# PCBschematic.net
KiCad netlist of a schematic drawn in EAGLE
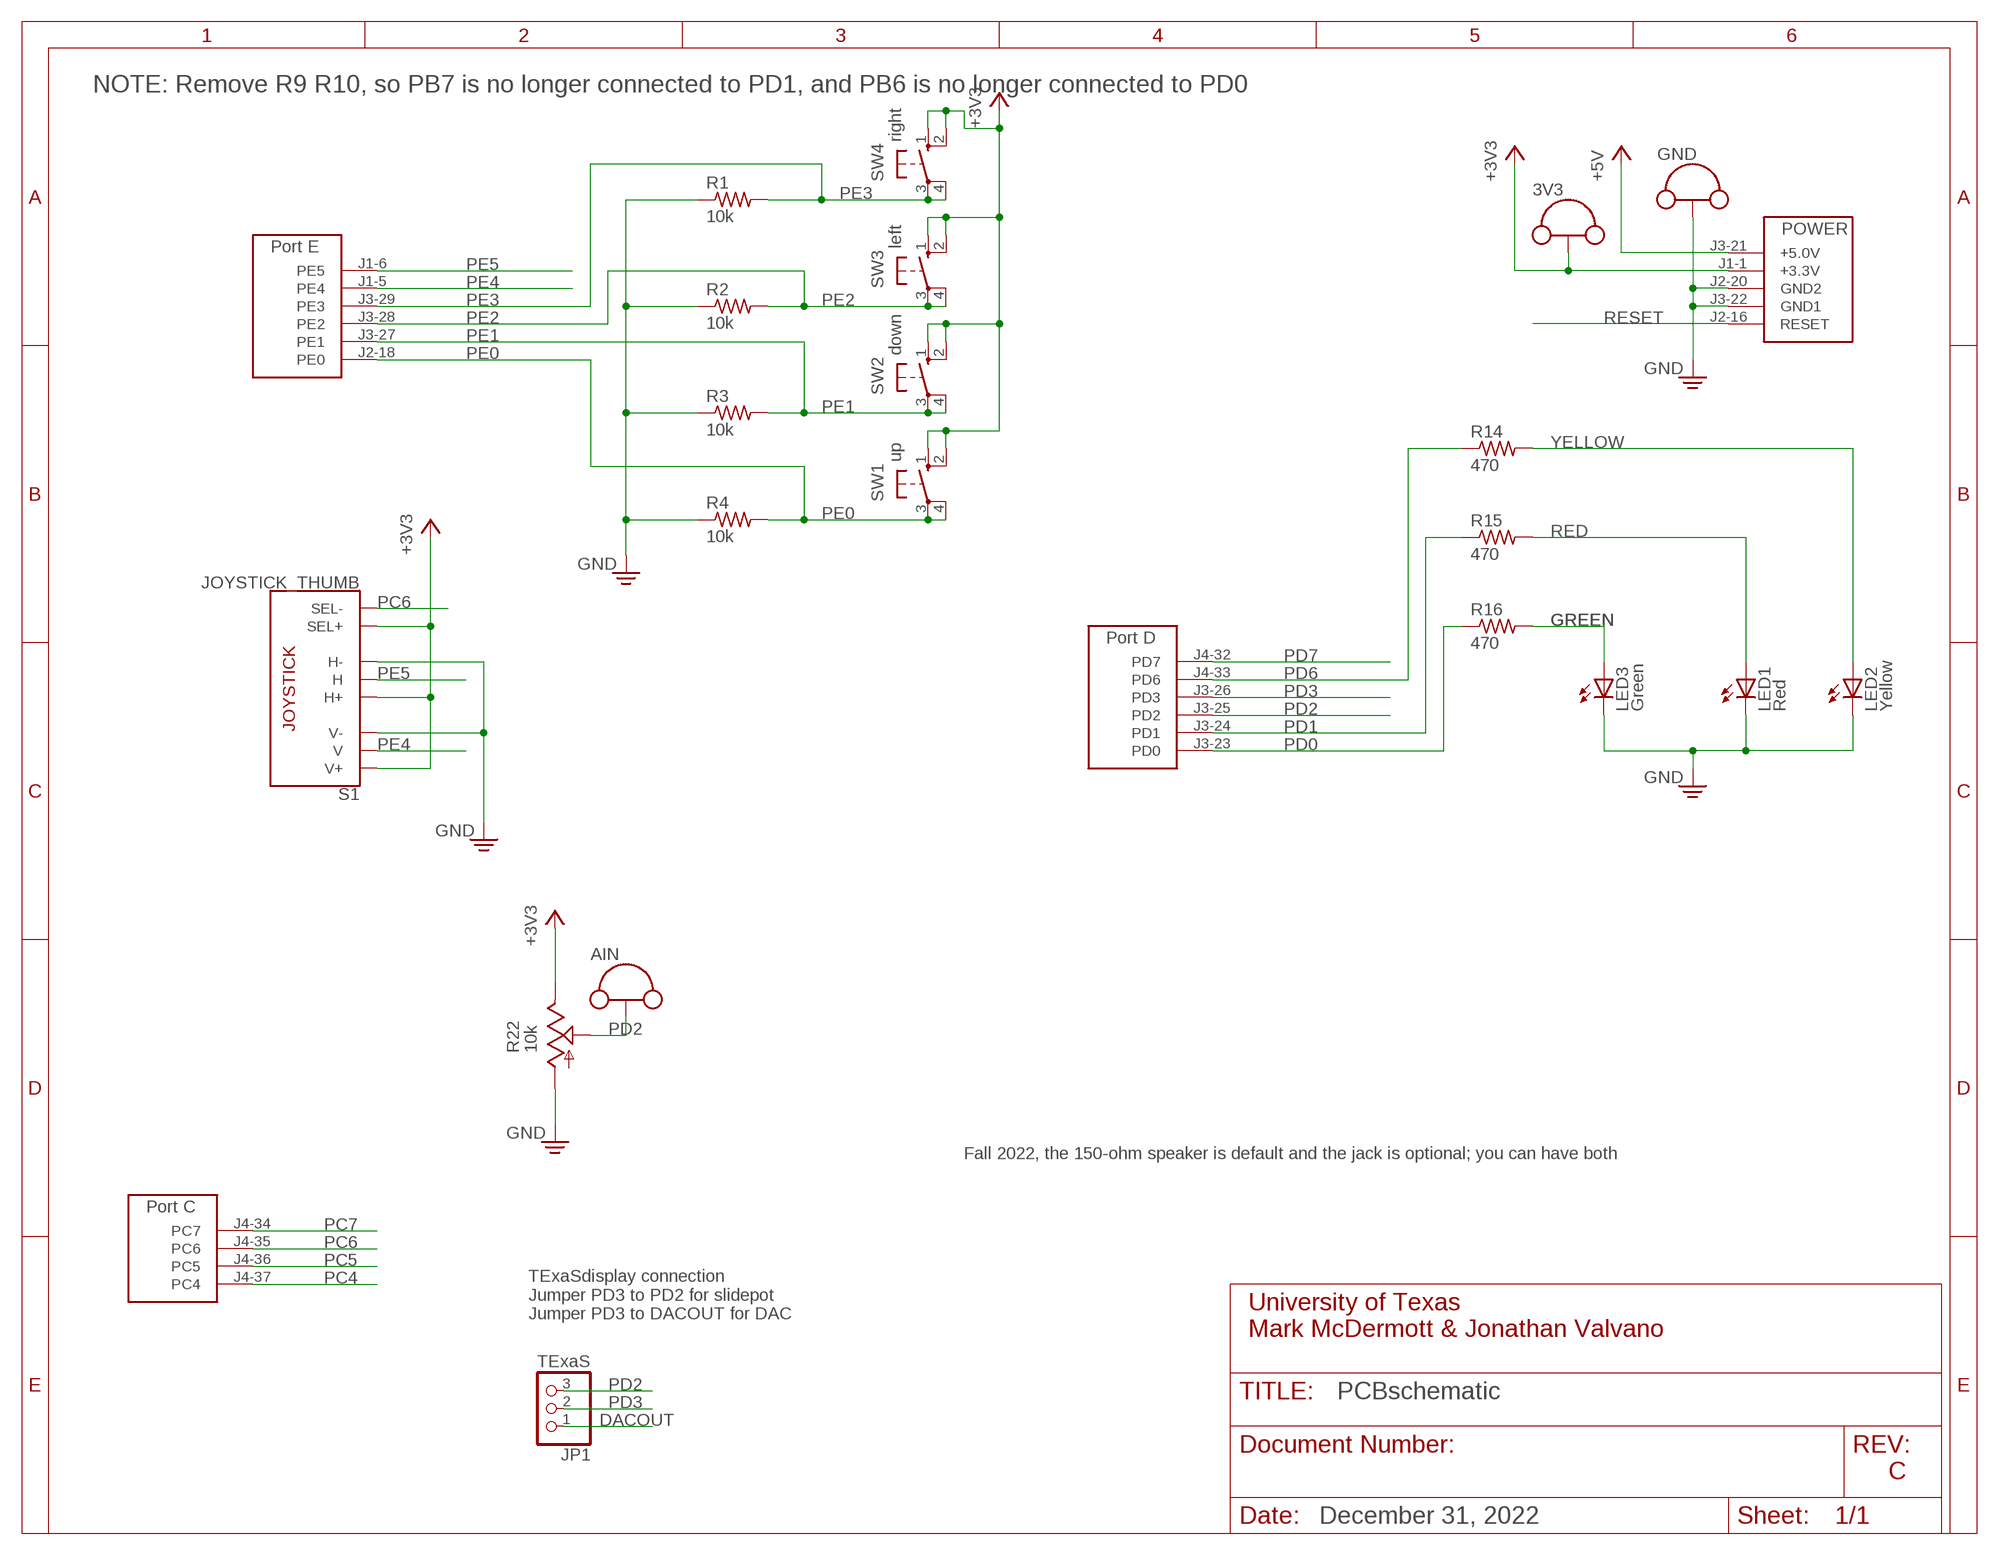
[diagram p0: schematic, sheet 1, part 1 of 2]
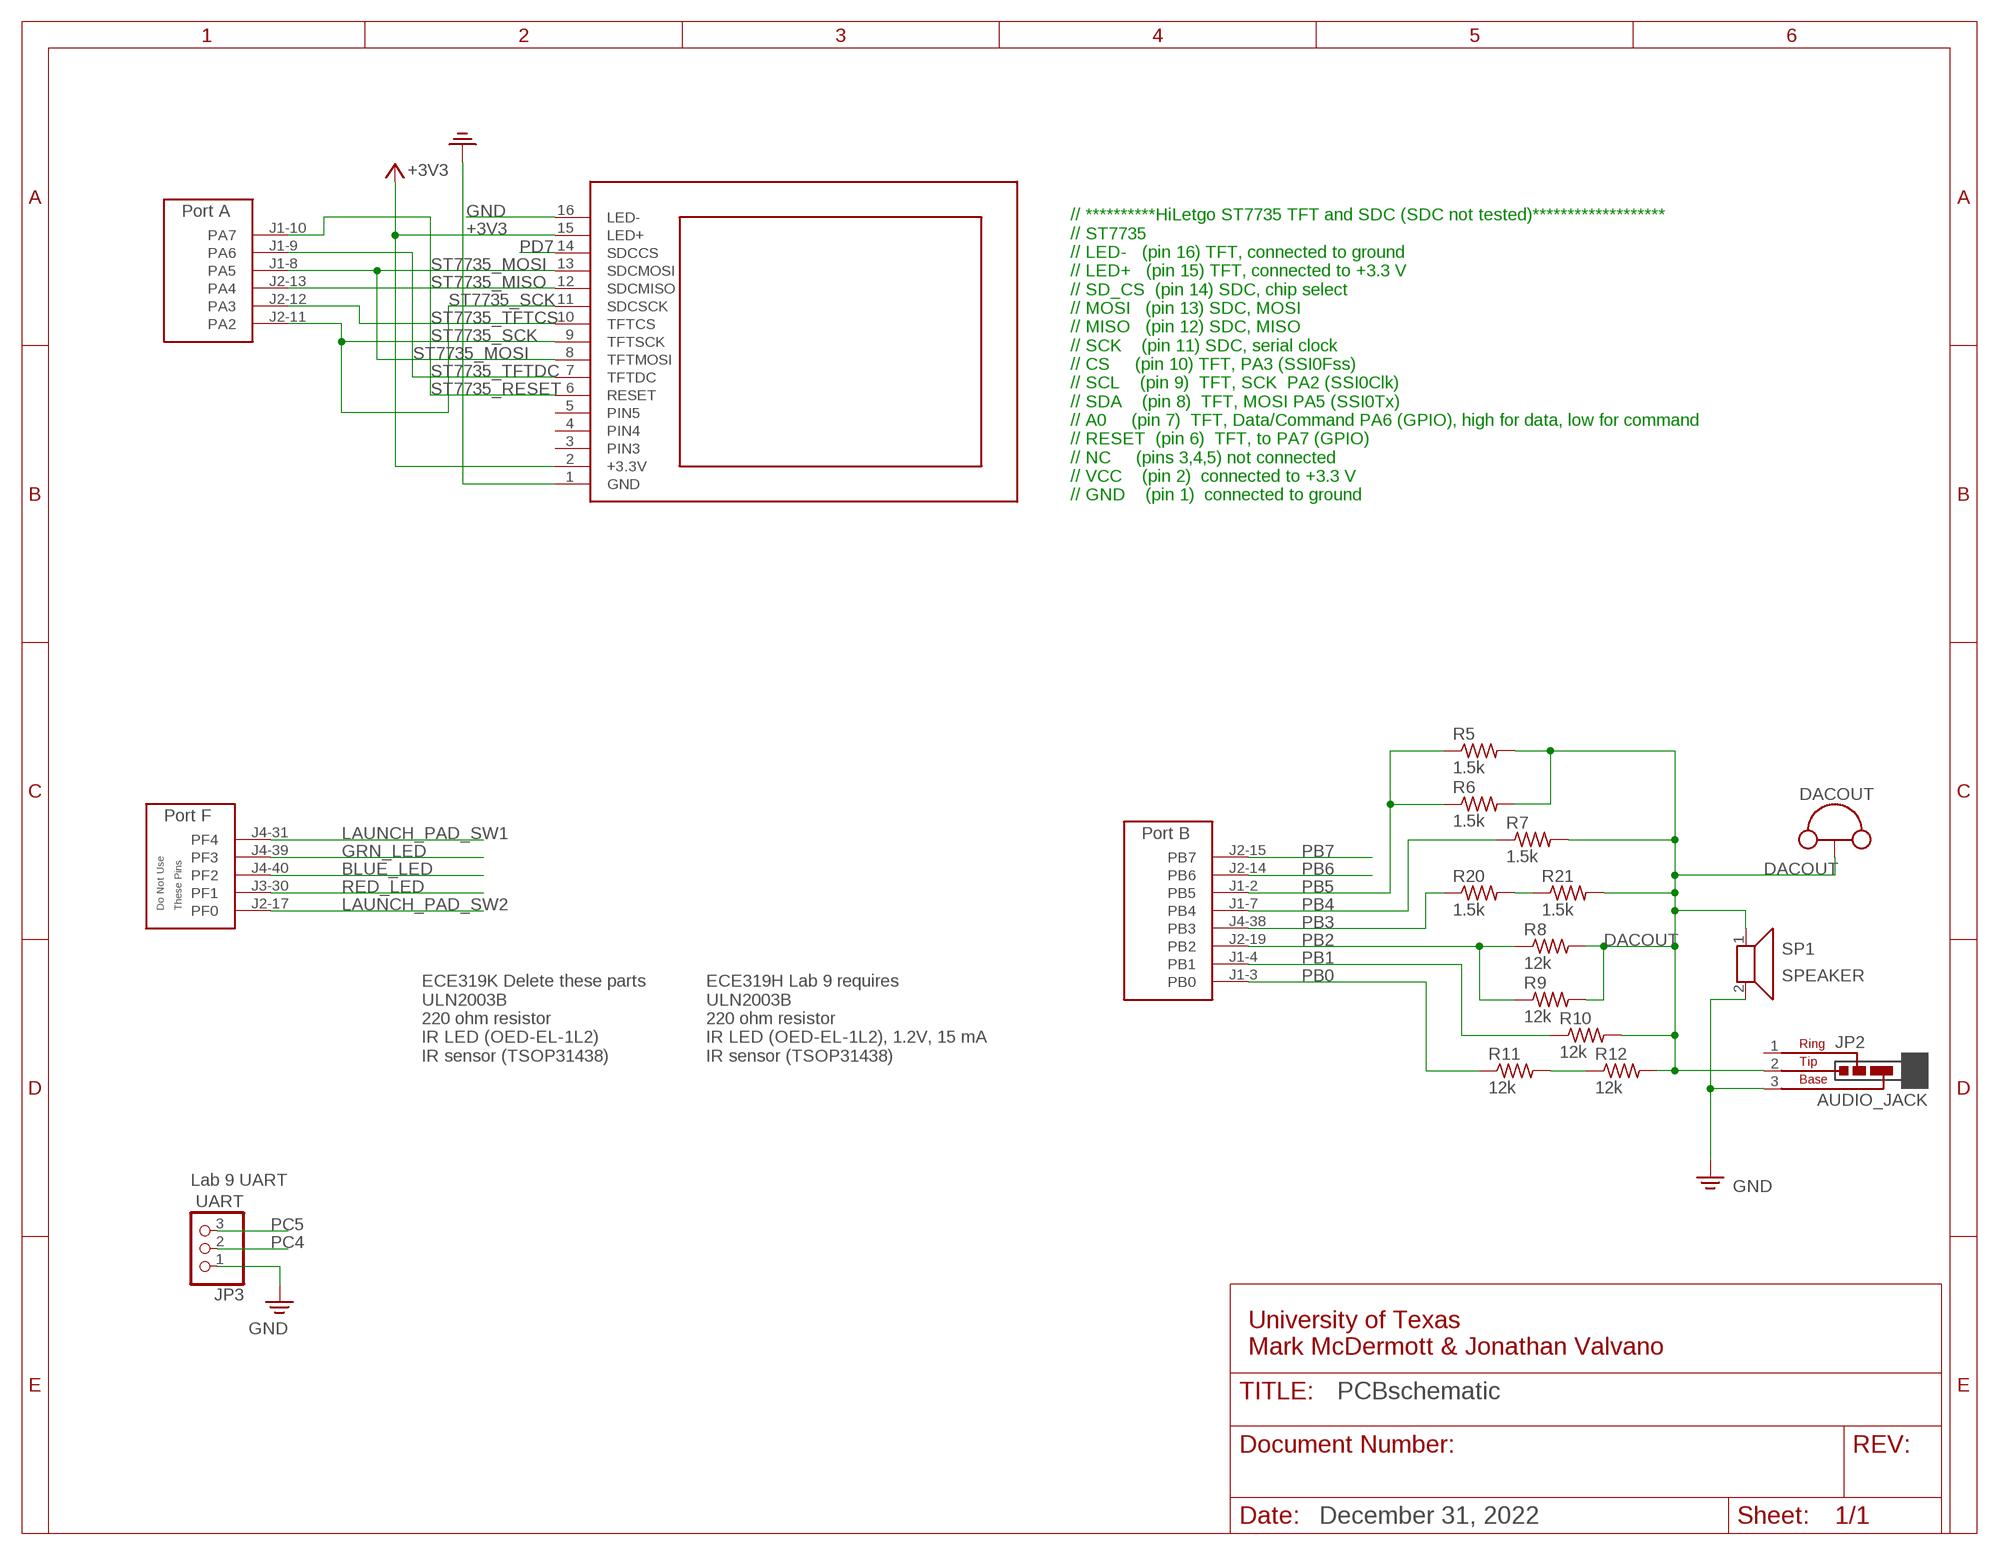
[diagram p1: schematic, sheet 1, part 2 of 2]

(export (version "E")
  (design (tool "Eeschema 10.0.6"))
  (components
    (comp (ref "3V3")
      (value "TP_LOOP")
      (footprint "eagle-import:TP_LOOP")
      (libsource (lib "eagle-import") (part "TP_LOOP"))
    )
    (comp (ref "AIN")
      (value "TP_LOOP")
      (footprint "eagle-import:TP_LOOP")
      (libsource (lib "eagle-import") (part "TP_LOOP"))
    )
    (comp (ref "DACOUT")
      (value "TP_LOOP")
      (footprint "eagle-import:TP_LOOP")
      (libsource (lib "eagle-import") (part "TP_LOOP"))
    )
    (comp (ref "GND")
      (value "TP_LOOP")
      (footprint "eagle-import:TP_LOOP")
      (libsource (lib "eagle-import") (part "TP_LOOP"))
    )
    (comp (ref "JP1")
      (value "TExaS")
      (footprint "eagle-import:1X03")
      (libsource (lib "eagle-import") (part "PINHD-1X3"))
    )
    (comp (ref "JP2")
      (value "AUDIO_JACK")
      (footprint "eagle-import:JACK")
      (libsource (lib "eagle-import") (part "AUDIO_JACK"))
    )
    (comp (ref "JP3")
      (value "UART")
      (footprint "eagle-import:1X03")
      (libsource (lib "eagle-import") (part "PINHD-1X3"))
    )
    (comp (ref "LED1")
      (value "Red")
      (footprint "eagle-import:LED5MM")
      (libsource (lib "eagle-import") (part "LED5MM"))
    )
    (comp (ref "LED2")
      (value "Yellow")
      (footprint "eagle-import:LED5MM")
      (libsource (lib "eagle-import") (part "LED5MM"))
    )
    (comp (ref "LED3")
      (value "Green")
      (footprint "eagle-import:LED5MM")
      (libsource (lib "eagle-import") (part "LED5MM"))
    )
    (comp (ref "R1")
      (value "10k")
      (footprint "eagle-import:RES300MIL")
      (libsource (lib "eagle-import") (part "RESISTOR0204/7"))
    )
    (comp (ref "R2")
      (value "10k")
      (footprint "eagle-import:RES300MIL")
      (libsource (lib "eagle-import") (part "RESISTOR0204/7"))
    )
    (comp (ref "R3")
      (value "10k")
      (footprint "eagle-import:RES300MIL")
      (libsource (lib "eagle-import") (part "RESISTOR0204/7"))
    )
    (comp (ref "R4")
      (value "10k")
      (footprint "eagle-import:RES300MIL")
      (libsource (lib "eagle-import") (part "RESISTOR0204/7"))
    )
    (comp (ref "R5")
      (value "1.5k")
      (footprint "eagle-import:RES300MIL")
      (libsource (lib "eagle-import") (part "RESISTOR0204/7"))
    )
    (comp (ref "R6")
      (value "1.5k")
      (footprint "eagle-import:RES300MIL")
      (libsource (lib "eagle-import") (part "RESISTOR0204/7"))
    )
    (comp (ref "R7")
      (value "1.5k")
      (footprint "eagle-import:RES300MIL")
      (libsource (lib "eagle-import") (part "RESISTOR0204/7"))
    )
    (comp (ref "R8")
      (value "12k")
      (footprint "eagle-import:RES300MIL")
      (libsource (lib "eagle-import") (part "RESISTOR0204/7"))
    )
    (comp (ref "R9")
      (value "12k")
      (footprint "eagle-import:RES300MIL")
      (libsource (lib "eagle-import") (part "RESISTOR0204/7"))
    )
    (comp (ref "R10")
      (value "12k")
      (footprint "eagle-import:RES300MIL")
      (libsource (lib "eagle-import") (part "RESISTOR0204/7"))
    )
    (comp (ref "R11")
      (value "12k")
      (footprint "eagle-import:RES300MIL")
      (libsource (lib "eagle-import") (part "RESISTOR0204/7"))
    )
    (comp (ref "R12")
      (value "12k")
      (footprint "eagle-import:RES300MIL")
      (libsource (lib "eagle-import") (part "RESISTOR0204/7"))
    )
    (comp (ref "R14")
      (value "470")
      (footprint "eagle-import:RES300MIL")
      (libsource (lib "eagle-import") (part "RESISTOR0204/7"))
    )
    (comp (ref "R15")
      (value "470")
      (footprint "eagle-import:RES300MIL")
      (libsource (lib "eagle-import") (part "RESISTOR0204/7"))
    )
    (comp (ref "R16")
      (value "470")
      (footprint "eagle-import:RES300MIL")
      (libsource (lib "eagle-import") (part "RESISTOR0204/7"))
    )
    (comp (ref "R20")
      (value "1.5k")
      (footprint "eagle-import:RES300MIL")
      (libsource (lib "eagle-import") (part "RESISTOR0204/7"))
    )
    (comp (ref "R21")
      (value "1.5k")
      (footprint "eagle-import:RES300MIL")
      (libsource (lib "eagle-import") (part "RESISTOR0204/7"))
    )
    (comp (ref "R22")
      (value "10k")
      (footprint "eagle-import:PTA2043")
      (libsource (lib "eagle-import") (part "POTENTIOMETER_PTA2043B25U"))
    )
    (comp (ref "S1")
      (value "JOYSTICK_THUMB")
      (footprint "eagle-import:JOYSTICK")
      (libsource (lib "eagle-import") (part "JOYSTICK_THUMB"))
    )
    (comp (ref "SP1")
      (value "SPEAKER")
      (footprint "eagle-import:1X02")
      (libsource (lib "eagle-import") (part "SPEAKER"))
    )
    (comp (ref "ST7735_LCD")
      (value "HILETGO")
      (footprint "eagle-import:HILETGO")
      (libsource (lib "eagle-import") (part "HILETGO"))
    )
    (comp (ref "SW1")
      (value "up")
      (footprint "eagle-import:B3F-10XX")
      (fields (field (name "MPN") "B3F-1000"))
      (libsource (lib "eagle-import") (part "B3F-1052"))
    )
    (comp (ref "SW2")
      (value "down")
      (footprint "eagle-import:B3F-10XX")
      (fields (field (name "MPN") "B3F-1000"))
      (libsource (lib "eagle-import") (part "B3F-1052"))
    )
    (comp (ref "SW3")
      (value "left")
      (footprint "eagle-import:B3F-10XX")
      (fields (field (name "MPN") "B3F-1000"))
      (libsource (lib "eagle-import") (part "B3F-1052"))
    )
    (comp (ref "SW4")
      (value "right")
      (footprint "eagle-import:B3F-10XX")
      (fields (field (name "MPN") "B3F-1000"))
      (libsource (lib "eagle-import") (part "B3F-1052"))
    )
    (comp (ref "U$2")
      (value "TM4C_BP")
      (footprint "eagle-import:TM4C_BOOSTER_PACK")
      (libsource (lib "eagle-import") (part "TM4C_BP"))
    )
  )
  (nets
    (net (code "1") (name "+3V3") (class "Default")
      (node (ref "3V3") (pin "P$1") (pinfunction "TP_P$1") (pintype "bidirectional"))
      (node (ref "3V3") (pin "P$2") (pinfunction "TP_P$2") (pintype "bidirectional"))
      (node (ref "R22") (pin "1") (pinfunction "E_1") (pintype "passive"))
      (node (ref "S1") (pin "B1A") (pinfunction "SEL+_B1A") (pintype "bidirectional"))
      (node (ref "S1") (pin "H1") (pinfunction "H+_H1") (pintype "bidirectional"))
      (node (ref "S1") (pin "V1") (pinfunction "V+_V1") (pintype "bidirectional"))
      (node (ref "ST7735_LCD") (pin "15") (pinfunction "LED+_15") (pintype "bidirectional"))
      (node (ref "ST7735_LCD") (pin "2") (pinfunction "+3.3V_2") (pintype "bidirectional"))
      (node (ref "SW1") (pin "1") (pinfunction "S_1") (pintype "passive"))
      (node (ref "SW1") (pin "2") (pinfunction "S1_2") (pintype "passive"))
      (node (ref "SW2") (pin "1") (pinfunction "S_1") (pintype "passive"))
      (node (ref "SW2") (pin "2") (pinfunction "S1_2") (pintype "passive"))
      (node (ref "SW3") (pin "1") (pinfunction "S_1") (pintype "passive"))
      (node (ref "SW3") (pin "2") (pinfunction "S1_2") (pintype "passive"))
      (node (ref "SW4") (pin "1") (pinfunction "S_1") (pintype "passive"))
      (node (ref "SW4") (pin "2") (pinfunction "S1_2") (pintype "passive"))
      (node (ref "U$2") (pin "J1-1") (pinfunction "+3.3V_J1-1") (pintype "bidirectional"))
    )
    (net (code "2") (name "+5V") (class "Default")
      (node (ref "U$2") (pin "J3-21") (pinfunction "+5.0V_J3-21") (pintype "bidirectional"))
    )
    (net (code "3") (name "/BLUE_LED") (class "Default")
      (node (ref "U$2") (pin "J4-40") (pinfunction "PF2_J4-40") (pintype "bidirectional"))
    )
    (net (code "4") (name "/DACOUT") (class "Default")
      (node (ref "DACOUT") (pin "P$1") (pinfunction "TP_P$1") (pintype "bidirectional"))
      (node (ref "DACOUT") (pin "P$2") (pinfunction "TP_P$2") (pintype "bidirectional"))
      (node (ref "JP1") (pin "1") (pinfunction "1_1") (pintype "passive"))
      (node (ref "JP2") (pin "2") (pinfunction "TIP_2") (pintype "passive"))
      (node (ref "R10") (pin "2") (pinfunction "2_2") (pintype "passive"))
      (node (ref "R12") (pin "2") (pinfunction "2_2") (pintype "passive"))
      (node (ref "R21") (pin "2") (pinfunction "2_2") (pintype "passive"))
      (node (ref "R5") (pin "2") (pinfunction "2_2") (pintype "passive"))
      (node (ref "R6") (pin "2") (pinfunction "2_2") (pintype "passive"))
      (node (ref "R7") (pin "2") (pinfunction "2_2") (pintype "passive"))
      (node (ref "R8") (pin "2") (pinfunction "2_2") (pintype "passive"))
      (node (ref "R9") (pin "2") (pinfunction "2_2") (pintype "passive"))
      (node (ref "SP1") (pin "1") (pinfunction "1_1") (pintype "passive"))
    )
    (net (code "5") (name "/GREEN") (class "Default")
      (node (ref "LED3") (pin "A") (pinfunction "A_A") (pintype "passive"))
      (node (ref "R16") (pin "2") (pinfunction "2_2") (pintype "passive"))
    )
    (net (code "6") (name "/GRN_LED") (class "Default")
      (node (ref "U$2") (pin "J4-39") (pinfunction "PF3_J4-39") (pintype "bidirectional"))
    )
    (net (code "7") (name "/LAUNCH_PAD_SW1") (class "Default")
      (node (ref "U$2") (pin "J4-31") (pinfunction "PF4_J4-31") (pintype "bidirectional"))
    )
    (net (code "8") (name "/LAUNCH_PAD_SW2") (class "Default")
      (node (ref "U$2") (pin "J2-17") (pinfunction "PF0_J2-17") (pintype "bidirectional"))
    )
    (net (code "9") (name "/PB0") (class "Default")
      (node (ref "R11") (pin "1") (pinfunction "1_1") (pintype "passive"))
      (node (ref "U$2") (pin "J1-3") (pinfunction "PB0_J1-3") (pintype "bidirectional"))
    )
    (net (code "10") (name "/PB1") (class "Default")
      (node (ref "R10") (pin "1") (pinfunction "1_1") (pintype "passive"))
      (node (ref "U$2") (pin "J1-4") (pinfunction "PB1_J1-4") (pintype "bidirectional"))
    )
    (net (code "11") (name "/PB2") (class "Default")
      (node (ref "R8") (pin "1") (pinfunction "1_1") (pintype "passive"))
      (node (ref "R9") (pin "1") (pinfunction "1_1") (pintype "passive"))
      (node (ref "U$2") (pin "J2-19") (pinfunction "PB2_J2-19") (pintype "bidirectional"))
    )
    (net (code "12") (name "/PB3") (class "Default")
      (node (ref "R20") (pin "1") (pinfunction "1_1") (pintype "passive"))
      (node (ref "U$2") (pin "J4-38") (pinfunction "PB3_J4-38") (pintype "bidirectional"))
    )
    (net (code "13") (name "/PB4") (class "Default")
      (node (ref "R7") (pin "1") (pinfunction "1_1") (pintype "passive"))
      (node (ref "U$2") (pin "J1-7") (pinfunction "PB4_J1-7") (pintype "bidirectional"))
    )
    (net (code "14") (name "/PB5") (class "Default")
      (node (ref "R5") (pin "1") (pinfunction "1_1") (pintype "passive"))
      (node (ref "R6") (pin "1") (pinfunction "1_1") (pintype "passive"))
      (node (ref "U$2") (pin "J1-2") (pinfunction "PB5_J1-2") (pintype "bidirectional"))
    )
    (net (code "15") (name "/PB6") (class "Default")
      (node (ref "U$2") (pin "J2-14") (pinfunction "PB6_J2-14") (pintype "bidirectional"))
    )
    (net (code "16") (name "/PB7") (class "Default")
      (node (ref "U$2") (pin "J2-15") (pinfunction "PB7_J2-15") (pintype "bidirectional"))
    )
    (net (code "17") (name "/PC4") (class "Default")
      (node (ref "JP3") (pin "2") (pinfunction "2_2") (pintype "passive"))
      (node (ref "U$2") (pin "J4-37") (pinfunction "PC4_J4-37") (pintype "bidirectional"))
    )
    (net (code "18") (name "/PC5") (class "Default")
      (node (ref "JP3") (pin "3") (pinfunction "3_3") (pintype "passive"))
      (node (ref "U$2") (pin "J4-36") (pinfunction "PC5_J4-36") (pintype "bidirectional"))
    )
    (net (code "19") (name "/PC6") (class "Default")
      (node (ref "S1") (pin "B2A") (pinfunction "SEL-_B2A") (pintype "bidirectional"))
      (node (ref "U$2") (pin "J4-35") (pinfunction "PC6_J4-35") (pintype "bidirectional"))
    )
    (net (code "20") (name "/PC7") (class "Default")
      (node (ref "U$2") (pin "J4-34") (pinfunction "PC7_J4-34") (pintype "bidirectional"))
    )
    (net (code "21") (name "/PD0") (class "Default")
      (node (ref "R16") (pin "1") (pinfunction "1_1") (pintype "passive"))
      (node (ref "U$2") (pin "J3-23") (pinfunction "PD0_J3-23") (pintype "bidirectional"))
    )
    (net (code "22") (name "/PD1") (class "Default")
      (node (ref "R15") (pin "1") (pinfunction "1_1") (pintype "passive"))
      (node (ref "U$2") (pin "J3-24") (pinfunction "PD1_J3-24") (pintype "bidirectional"))
    )
    (net (code "23") (name "/PD2") (class "Default")
      (node (ref "AIN") (pin "P$1") (pinfunction "TP_P$1") (pintype "bidirectional"))
      (node (ref "AIN") (pin "P$2") (pinfunction "TP_P$2") (pintype "bidirectional"))
      (node (ref "JP1") (pin "3") (pinfunction "3_3") (pintype "passive"))
      (node (ref "R22") (pin "2") (pinfunction "S_2") (pintype "passive"))
      (node (ref "U$2") (pin "J3-25") (pinfunction "PD2_J3-25") (pintype "bidirectional"))
    )
    (net (code "24") (name "/PD3") (class "Default")
      (node (ref "JP1") (pin "2") (pinfunction "2_2") (pintype "passive"))
      (node (ref "U$2") (pin "J3-26") (pinfunction "PD3_J3-26") (pintype "bidirectional"))
    )
    (net (code "25") (name "/PD6") (class "Default")
      (node (ref "R14") (pin "1") (pinfunction "1_1") (pintype "passive"))
      (node (ref "U$2") (pin "J4-33") (pinfunction "PD6_J4-33") (pintype "bidirectional"))
    )
    (net (code "26") (name "/PD7") (class "Default")
      (node (ref "ST7735_LCD") (pin "14") (pinfunction "SDCCS_14") (pintype "bidirectional"))
      (node (ref "U$2") (pin "J4-32") (pinfunction "PD7_J4-32") (pintype "bidirectional"))
    )
    (net (code "27") (name "/PE0") (class "Default")
      (node (ref "R4") (pin "2") (pinfunction "2_2") (pintype "passive"))
      (node (ref "SW1") (pin "3") (pinfunction "P_3") (pintype "passive"))
      (node (ref "SW1") (pin "4") (pinfunction "P1_4") (pintype "passive"))
      (node (ref "U$2") (pin "J2-18") (pinfunction "PE0_J2-18") (pintype "bidirectional"))
    )
    (net (code "28") (name "/PE1") (class "Default")
      (node (ref "R3") (pin "2") (pinfunction "2_2") (pintype "passive"))
      (node (ref "SW2") (pin "3") (pinfunction "P_3") (pintype "passive"))
      (node (ref "SW2") (pin "4") (pinfunction "P1_4") (pintype "passive"))
      (node (ref "U$2") (pin "J3-27") (pinfunction "PE1_J3-27") (pintype "bidirectional"))
    )
    (net (code "29") (name "/PE2") (class "Default")
      (node (ref "R2") (pin "2") (pinfunction "2_2") (pintype "passive"))
      (node (ref "SW3") (pin "3") (pinfunction "P_3") (pintype "passive"))
      (node (ref "SW3") (pin "4") (pinfunction "P1_4") (pintype "passive"))
      (node (ref "U$2") (pin "J3-28") (pinfunction "PE2_J3-28") (pintype "bidirectional"))
    )
    (net (code "30") (name "/PE3") (class "Default")
      (node (ref "R1") (pin "2") (pinfunction "2_2") (pintype "passive"))
      (node (ref "SW4") (pin "3") (pinfunction "P_3") (pintype "passive"))
      (node (ref "SW4") (pin "4") (pinfunction "P1_4") (pintype "passive"))
      (node (ref "U$2") (pin "J3-29") (pinfunction "PE3_J3-29") (pintype "bidirectional"))
    )
    (net (code "31") (name "/PE4") (class "Default")
      (node (ref "S1") (pin "V2") (pinfunction "V_V2") (pintype "bidirectional"))
      (node (ref "U$2") (pin "J1-5") (pinfunction "PE4_J1-5") (pintype "bidirectional"))
    )
    (net (code "32") (name "/PE5") (class "Default")
      (node (ref "S1") (pin "H2") (pinfunction "H_H2") (pintype "bidirectional"))
      (node (ref "U$2") (pin "J1-6") (pinfunction "PE5_J1-6") (pintype "bidirectional"))
    )
    (net (code "33") (name "/RED") (class "Default")
      (node (ref "LED1") (pin "A") (pinfunction "A_A") (pintype "passive"))
      (node (ref "R15") (pin "2") (pinfunction "2_2") (pintype "passive"))
    )
    (net (code "34") (name "/RED_LED") (class "Default")
      (node (ref "U$2") (pin "J3-30") (pinfunction "PF1_J3-30") (pintype "bidirectional"))
    )
    (net (code "35") (name "/RESET") (class "Default")
      (node (ref "U$2") (pin "J2-16") (pinfunction "RESET_J2-16") (pintype "bidirectional"))
    )
    (net (code "36") (name "/ST7735_MISO") (class "Default")
      (node (ref "ST7735_LCD") (pin "12") (pinfunction "SDCMISO_12") (pintype "bidirectional"))
      (node (ref "U$2") (pin "J2-13") (pinfunction "PA4_J2-13") (pintype "bidirectional"))
    )
    (net (code "37") (name "/ST7735_MOSI") (class "Default")
      (node (ref "ST7735_LCD") (pin "13") (pinfunction "SDCMOSI_13") (pintype "bidirectional"))
      (node (ref "ST7735_LCD") (pin "8") (pinfunction "TFTMOSI_8") (pintype "bidirectional"))
      (node (ref "U$2") (pin "J1-8") (pinfunction "PA5_J1-8") (pintype "bidirectional"))
    )
    (net (code "38") (name "/ST7735_RESET") (class "Default")
      (node (ref "ST7735_LCD") (pin "6") (pinfunction "RESET_6") (pintype "bidirectional"))
      (node (ref "U$2") (pin "J1-10") (pinfunction "PA7_J1-10") (pintype "bidirectional"))
    )
    (net (code "39") (name "/ST7735_SCK") (class "Default")
      (node (ref "ST7735_LCD") (pin "11") (pinfunction "SDCSCK_11") (pintype "bidirectional"))
      (node (ref "ST7735_LCD") (pin "9") (pinfunction "TFTSCK_9") (pintype "bidirectional"))
      (node (ref "U$2") (pin "J2-11") (pinfunction "PA2_J2-11") (pintype "bidirectional"))
    )
    (net (code "40") (name "/ST7735_TFTCS") (class "Default")
      (node (ref "ST7735_LCD") (pin "10") (pinfunction "TFTCS_10") (pintype "bidirectional"))
      (node (ref "U$2") (pin "J2-12") (pinfunction "PA3_J2-12") (pintype "bidirectional"))
    )
    (net (code "41") (name "/ST7735_TFTDC") (class "Default")
      (node (ref "ST7735_LCD") (pin "7") (pinfunction "TFTDC_7") (pintype "bidirectional"))
      (node (ref "U$2") (pin "J1-9") (pinfunction "PA6_J1-9") (pintype "bidirectional"))
    )
    (net (code "42") (name "/YELLOW") (class "Default")
      (node (ref "LED2") (pin "A") (pinfunction "A_A") (pintype "passive"))
      (node (ref "R14") (pin "2") (pinfunction "2_2") (pintype "passive"))
    )
    (net (code "43") (name "GND") (class "Default")
      (node (ref "GND") (pin "P$1") (pinfunction "TP_P$1") (pintype "bidirectional"))
      (node (ref "GND") (pin "P$2") (pinfunction "TP_P$2") (pintype "bidirectional"))
      (node (ref "JP2") (pin "3") (pinfunction "BASE_3") (pintype "passive"))
      (node (ref "JP3") (pin "1") (pinfunction "1_1") (pintype "passive"))
      (node (ref "LED1") (pin "K") (pinfunction "C_K") (pintype "passive"))
      (node (ref "LED2") (pin "K") (pinfunction "C_K") (pintype "passive"))
      (node (ref "LED3") (pin "K") (pinfunction "C_K") (pintype "passive"))
      (node (ref "R1") (pin "1") (pinfunction "1_1") (pintype "passive"))
      (node (ref "R2") (pin "1") (pinfunction "1_1") (pintype "passive"))
      (node (ref "R22") (pin "3") (pinfunction "A_3") (pintype "passive"))
      (node (ref "R3") (pin "1") (pinfunction "1_1") (pintype "passive"))
      (node (ref "R4") (pin "1") (pinfunction "1_1") (pintype "passive"))
      (node (ref "S1") (pin "H3") (pinfunction "H-_H3") (pintype "bidirectional"))
      (node (ref "S1") (pin "V3") (pinfunction "V-_V3") (pintype "bidirectional"))
      (node (ref "SP1") (pin "2") (pinfunction "2_2") (pintype "passive"))
      (node (ref "ST7735_LCD") (pin "1") (pinfunction "GND_1") (pintype "bidirectional"))
      (node (ref "ST7735_LCD") (pin "16") (pinfunction "LED-_16") (pintype "bidirectional"))
      (node (ref "U$2") (pin "J2-20") (pinfunction "GND2_J2-20") (pintype "bidirectional"))
      (node (ref "U$2") (pin "J3-22") (pinfunction "GND1_J3-22") (pintype "bidirectional"))
    )
    (net (code "44") (name "Net-(R11-Pad2)") (class "Default")
      (node (ref "R11") (pin "2") (pinfunction "2_2") (pintype "passive"))
      (node (ref "R12") (pin "1") (pinfunction "1_1") (pintype "passive"))
    )
    (net (code "45") (name "Net-(R20-Pad2)") (class "Default")
      (node (ref "R20") (pin "2") (pinfunction "2_2") (pintype "passive"))
      (node (ref "R21") (pin "1") (pinfunction "1_1") (pintype "passive"))
    )
    (net (code "46") (name "unconnected-(JP2-RING-Pad1)") (class "Default")
      (node (ref "JP2") (pin "1") (pinfunction "RING_1") (pintype "passive"))
    )
    (net (code "47") (name "unconnected-(ST7735_LCD-PIN3-Pad3)") (class "Default")
      (node (ref "ST7735_LCD") (pin "3") (pinfunction "PIN3_3") (pintype "bidirectional"))
    )
    (net (code "48") (name "unconnected-(ST7735_LCD-PIN4-Pad4)") (class "Default")
      (node (ref "ST7735_LCD") (pin "4") (pinfunction "PIN4_4") (pintype "bidirectional"))
    )
    (net (code "49") (name "unconnected-(ST7735_LCD-PIN5-Pad5)") (class "Default")
      (node (ref "ST7735_LCD") (pin "5") (pinfunction "PIN5_5") (pintype "bidirectional"))
    )
  )
)
